# Z80TestCircuit.net
KiCad netlist of a schematic drawn in EAGLE
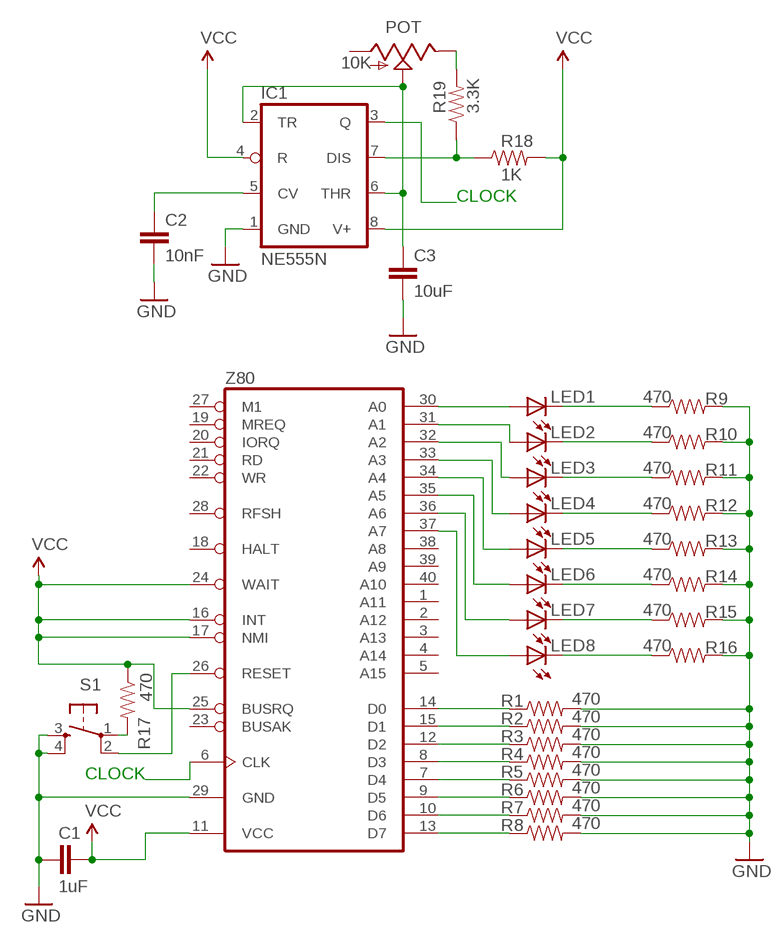
[diagram p0: schematic, sheet 1]

(export (version "E")
  (design (tool "Eeschema 10.0.6"))
  (components
    (comp (ref "C1")
      (value "1uF")
      (footprint "eagle-import:E5-5")
      (libsource (lib "eagle-import") (part "CAP"))
    )
    (comp (ref "C2")
      (value "10nF")
      (footprint "eagle-import:E5-5")
      (libsource (lib "eagle-import") (part "CAP"))
    )
    (comp (ref "C3")
      (value "10uF")
      (footprint "eagle-import:E5-5")
      (libsource (lib "eagle-import") (part "CAP"))
    )
    (comp (ref "IC1")
      (value "NE555N")
      (footprint "eagle-import:DIL08-ROUND")
      (libsource (lib "eagle-import") (part "555NNE"))
    )
    (comp (ref "LED1")
      (value "LED5MM")
      (footprint "eagle-import:LED5MM")
      (libsource (lib "eagle-import") (part "LED5MM"))
    )
    (comp (ref "LED2")
      (value "LED5MM")
      (footprint "eagle-import:LED5MM")
      (libsource (lib "eagle-import") (part "LED5MM"))
    )
    (comp (ref "LED3")
      (value "LED5MM")
      (footprint "eagle-import:LED5MM")
      (libsource (lib "eagle-import") (part "LED5MM"))
    )
    (comp (ref "LED4")
      (value "LED5MM")
      (footprint "eagle-import:LED5MM")
      (libsource (lib "eagle-import") (part "LED5MM"))
    )
    (comp (ref "LED5")
      (value "LED5MM")
      (footprint "eagle-import:LED5MM")
      (libsource (lib "eagle-import") (part "LED5MM"))
    )
    (comp (ref "LED6")
      (value "LED5MM")
      (footprint "eagle-import:LED5MM")
      (libsource (lib "eagle-import") (part "LED5MM"))
    )
    (comp (ref "LED7")
      (value "LED5MM")
      (footprint "eagle-import:LED5MM")
      (libsource (lib "eagle-import") (part "LED5MM"))
    )
    (comp (ref "LED8")
      (value "LED5MM")
      (footprint "eagle-import:LED5MM")
      (libsource (lib "eagle-import") (part "LED5MM"))
    )
    (comp (ref "POT")
      (value "10K")
      (footprint "eagle-import:POT_ALPHA_RV16AF-20")
      (libsource (lib "eagle-import") (part "POT-RV16AF-20"))
    )
    (comp (ref "R1")
      (value "470")
      (footprint "eagle-import:AXIAL-0.4")
      (libsource (lib "eagle-import") (part "RESISTORPTH-1/4W"))
    )
    (comp (ref "R2")
      (value "470")
      (footprint "eagle-import:AXIAL-0.4")
      (libsource (lib "eagle-import") (part "RESISTORPTH-1/4W"))
    )
    (comp (ref "R3")
      (value "470")
      (footprint "eagle-import:AXIAL-0.4")
      (libsource (lib "eagle-import") (part "RESISTORPTH-1/4W"))
    )
    (comp (ref "R4")
      (value "470")
      (footprint "eagle-import:AXIAL-0.4")
      (libsource (lib "eagle-import") (part "RESISTORPTH-1/4W"))
    )
    (comp (ref "R5")
      (value "470")
      (footprint "eagle-import:AXIAL-0.4")
      (libsource (lib "eagle-import") (part "RESISTORPTH-1/4W"))
    )
    (comp (ref "R6")
      (value "470")
      (footprint "eagle-import:AXIAL-0.4")
      (libsource (lib "eagle-import") (part "RESISTORPTH-1/4W"))
    )
    (comp (ref "R7")
      (value "470")
      (footprint "eagle-import:AXIAL-0.4")
      (libsource (lib "eagle-import") (part "RESISTORPTH-1/4W"))
    )
    (comp (ref "R8")
      (value "470")
      (footprint "eagle-import:AXIAL-0.4")
      (libsource (lib "eagle-import") (part "RESISTORPTH-1/4W"))
    )
    (comp (ref "R9")
      (value "470")
      (footprint "eagle-import:AXIAL-0.4")
      (libsource (lib "eagle-import") (part "RESISTORPTH-1/4W"))
    )
    (comp (ref "R10")
      (value "470")
      (footprint "eagle-import:AXIAL-0.4")
      (libsource (lib "eagle-import") (part "RESISTORPTH-1/4W"))
    )
    (comp (ref "R11")
      (value "470")
      (footprint "eagle-import:AXIAL-0.4")
      (libsource (lib "eagle-import") (part "RESISTORPTH-1/4W"))
    )
    (comp (ref "R12")
      (value "470")
      (footprint "eagle-import:AXIAL-0.4")
      (libsource (lib "eagle-import") (part "RESISTORPTH-1/4W"))
    )
    (comp (ref "R13")
      (value "470")
      (footprint "eagle-import:AXIAL-0.4")
      (libsource (lib "eagle-import") (part "RESISTORPTH-1/4W"))
    )
    (comp (ref "R14")
      (value "470")
      (footprint "eagle-import:AXIAL-0.4")
      (libsource (lib "eagle-import") (part "RESISTORPTH-1/4W"))
    )
    (comp (ref "R15")
      (value "470")
      (footprint "eagle-import:AXIAL-0.4")
      (libsource (lib "eagle-import") (part "RESISTORPTH-1/4W"))
    )
    (comp (ref "R16")
      (value "470")
      (footprint "eagle-import:AXIAL-0.4")
      (libsource (lib "eagle-import") (part "RESISTORPTH-1/4W"))
    )
    (comp (ref "R17")
      (value "470")
      (footprint "eagle-import:AXIAL-0.4")
      (libsource (lib "eagle-import") (part "RESISTORPTH-1/4W"))
    )
    (comp (ref "R18")
      (value "1K")
      (footprint "eagle-import:AXIAL-0.4")
      (libsource (lib "eagle-import") (part "RESISTORPTH-1/4W"))
    )
    (comp (ref "R19")
      (value "3.3K")
      (footprint "eagle-import:AXIAL-0.4")
      (libsource (lib "eagle-import") (part "RESISTORPTH-1/4W"))
    )
    (comp (ref "S1")
      (value "TAC_SWITCHPTH")
      (footprint "eagle-import:TACTILE-PTH")
      (libsource (lib "eagle-import") (part "TAC_SWITCHPTH"))
    )
    (comp (ref "Z80")
      (value "Z80CPU")
      (footprint "eagle-import:DIL40")
      (libsource (lib "eagle-import") (part "Z80CPU"))
    )
  )
  (nets
    (net (code "1") (name "GND") (class "Default")
      (node (ref "C1") (pin "-") (pinfunction "2_-") (pintype "passive"))
      (node (ref "C2") (pin "-") (pinfunction "2_-") (pintype "passive"))
      (node (ref "C3") (pin "-") (pinfunction "2_-") (pintype "passive"))
      (node (ref "IC1") (pin "1") (pinfunction "GND_1") (pintype "power_in"))
      (node (ref "R1") (pin "P$2") (pinfunction "2_P$2") (pintype "passive"))
      (node (ref "R10") (pin "P$2") (pinfunction "2_P$2") (pintype "passive"))
      (node (ref "R11") (pin "P$2") (pinfunction "2_P$2") (pintype "passive"))
      (node (ref "R12") (pin "P$2") (pinfunction "2_P$2") (pintype "passive"))
      (node (ref "R13") (pin "P$2") (pinfunction "2_P$2") (pintype "passive"))
      (node (ref "R14") (pin "P$2") (pinfunction "2_P$2") (pintype "passive"))
      (node (ref "R15") (pin "P$2") (pinfunction "2_P$2") (pintype "passive"))
      (node (ref "R16") (pin "P$2") (pinfunction "2_P$2") (pintype "passive"))
      (node (ref "R2") (pin "P$2") (pinfunction "2_P$2") (pintype "passive"))
      (node (ref "R3") (pin "P$2") (pinfunction "2_P$2") (pintype "passive"))
      (node (ref "R4") (pin "P$2") (pinfunction "2_P$2") (pintype "passive"))
      (node (ref "R5") (pin "P$2") (pinfunction "2_P$2") (pintype "passive"))
      (node (ref "R6") (pin "P$2") (pinfunction "2_P$2") (pintype "passive"))
      (node (ref "R7") (pin "P$2") (pinfunction "2_P$2") (pintype "passive"))
      (node (ref "R8") (pin "P$2") (pinfunction "2_P$2") (pintype "passive"))
      (node (ref "R9") (pin "P$2") (pinfunction "2_P$2") (pintype "passive"))
      (node (ref "S1") (pin "3") (pinfunction "3_3") (pintype "passive"))
      (node (ref "S1") (pin "4") (pinfunction "4_4") (pintype "passive"))
      (node (ref "Z80") (pin "29") (pinfunction "GND_29") (pintype "power_in"))
    )
    (net (code "2") (name "Net-(C2-1)") (class "Default")
      (node (ref "C2") (pin "+") (pinfunction "1_+") (pintype "passive"))
      (node (ref "IC1") (pin "5") (pinfunction "CV_5") (pintype "input"))
    )
    (net (code "3") (name "Net-(C3-1)") (class "Default")
      (node (ref "C3") (pin "+") (pinfunction "1_+") (pintype "passive"))
      (node (ref "IC1") (pin "2") (pinfunction "TR_2") (pintype "input"))
      (node (ref "IC1") (pin "6") (pinfunction "THR_6") (pintype "input"))
      (node (ref "POT") (pin "2") (pinfunction "S_2") (pintype "passive"))
    )
    (net (code "4") (name "Net-(IC1-DIS)") (class "Default")
      (node (ref "IC1") (pin "7") (pinfunction "DIS_7") (pintype "input"))
      (node (ref "R18") (pin "P$1") (pinfunction "1_P$1") (pintype "passive"))
      (node (ref "R19") (pin "P$1") (pinfunction "1_P$1") (pintype "passive"))
    )
    (net (code "5") (name "Net-(LED1-C)") (class "Default")
      (node (ref "LED1") (pin "K") (pinfunction "C_K") (pintype "passive"))
      (node (ref "R9") (pin "P$1") (pinfunction "1_P$1") (pintype "passive"))
    )
    (net (code "6") (name "Net-(LED2-C)") (class "Default")
      (node (ref "LED2") (pin "K") (pinfunction "C_K") (pintype "passive"))
      (node (ref "R10") (pin "P$1") (pinfunction "1_P$1") (pintype "passive"))
    )
    (net (code "7") (name "Net-(LED3-C)") (class "Default")
      (node (ref "LED3") (pin "K") (pinfunction "C_K") (pintype "passive"))
      (node (ref "R11") (pin "P$1") (pinfunction "1_P$1") (pintype "passive"))
    )
    (net (code "8") (name "Net-(LED4-C)") (class "Default")
      (node (ref "LED4") (pin "K") (pinfunction "C_K") (pintype "passive"))
      (node (ref "R12") (pin "P$1") (pinfunction "1_P$1") (pintype "passive"))
    )
    (net (code "9") (name "Net-(LED5-C)") (class "Default")
      (node (ref "LED5") (pin "K") (pinfunction "C_K") (pintype "passive"))
      (node (ref "R13") (pin "P$1") (pinfunction "1_P$1") (pintype "passive"))
    )
    (net (code "10") (name "Net-(LED6-C)") (class "Default")
      (node (ref "LED6") (pin "K") (pinfunction "C_K") (pintype "passive"))
      (node (ref "R14") (pin "P$1") (pinfunction "1_P$1") (pintype "passive"))
    )
    (net (code "11") (name "Net-(LED7-C)") (class "Default")
      (node (ref "LED7") (pin "K") (pinfunction "C_K") (pintype "passive"))
      (node (ref "R15") (pin "P$1") (pinfunction "1_P$1") (pintype "passive"))
    )
    (net (code "12") (name "Net-(LED8-C)") (class "Default")
      (node (ref "LED8") (pin "K") (pinfunction "C_K") (pintype "passive"))
      (node (ref "R16") (pin "P$1") (pinfunction "1_P$1") (pintype "passive"))
    )
    (net (code "13") (name "Net-(POT-E)") (class "Default")
      (node (ref "POT") (pin "3") (pinfunction "E_3") (pintype "passive"))
      (node (ref "R19") (pin "P$2") (pinfunction "2_P$2") (pintype "passive"))
    )
    (net (code "14") (name "Net-(R1-1)") (class "Default")
      (node (ref "R1") (pin "P$1") (pinfunction "1_P$1") (pintype "passive"))
      (node (ref "Z80") (pin "14") (pinfunction "D0_14") (pintype "bidirectional"))
    )
    (net (code "15") (name "Net-(R2-1)") (class "Default")
      (node (ref "R2") (pin "P$1") (pinfunction "1_P$1") (pintype "passive"))
      (node (ref "Z80") (pin "15") (pinfunction "D1_15") (pintype "bidirectional"))
    )
    (net (code "16") (name "Net-(R3-1)") (class "Default")
      (node (ref "R3") (pin "P$1") (pinfunction "1_P$1") (pintype "passive"))
      (node (ref "Z80") (pin "12") (pinfunction "D2_12") (pintype "bidirectional"))
    )
    (net (code "17") (name "Net-(R4-1)") (class "Default")
      (node (ref "R4") (pin "P$1") (pinfunction "1_P$1") (pintype "passive"))
      (node (ref "Z80") (pin "8") (pinfunction "D3_8") (pintype "bidirectional"))
    )
    (net (code "18") (name "Net-(R5-1)") (class "Default")
      (node (ref "R5") (pin "P$1") (pinfunction "1_P$1") (pintype "passive"))
      (node (ref "Z80") (pin "7") (pinfunction "D4_7") (pintype "bidirectional"))
    )
    (net (code "19") (name "Net-(R6-1)") (class "Default")
      (node (ref "R6") (pin "P$1") (pinfunction "1_P$1") (pintype "passive"))
      (node (ref "Z80") (pin "9") (pinfunction "D5_9") (pintype "bidirectional"))
    )
    (net (code "20") (name "Net-(R7-1)") (class "Default")
      (node (ref "R7") (pin "P$1") (pinfunction "1_P$1") (pintype "passive"))
      (node (ref "Z80") (pin "10") (pinfunction "D6_10") (pintype "bidirectional"))
    )
    (net (code "21") (name "Net-(R8-1)") (class "Default")
      (node (ref "R8") (pin "P$1") (pinfunction "1_P$1") (pintype "passive"))
      (node (ref "Z80") (pin "13") (pinfunction "D7_13") (pintype "bidirectional"))
    )
    (net (code "22") (name "Net-(R17-2)") (class "Default")
      (node (ref "R17") (pin "P$2") (pinfunction "2_P$2") (pintype "passive"))
      (node (ref "S1") (pin "1") (pinfunction "1_1") (pintype "passive"))
    )
    (net (code "23") (name "Net-(Z80-A0)") (class "Default")
      (node (ref "LED1") (pin "A") (pinfunction "A_A") (pintype "passive"))
      (node (ref "Z80") (pin "30") (pinfunction "A0_30") (pintype "output"))
    )
    (net (code "24") (name "Net-(Z80-A1)") (class "Default")
      (node (ref "LED2") (pin "A") (pinfunction "A_A") (pintype "passive"))
      (node (ref "Z80") (pin "31") (pinfunction "A1_31") (pintype "output"))
    )
    (net (code "25") (name "Net-(Z80-A2)") (class "Default")
      (node (ref "LED3") (pin "A") (pinfunction "A_A") (pintype "passive"))
      (node (ref "Z80") (pin "32") (pinfunction "A2_32") (pintype "output"))
    )
    (net (code "26") (name "Net-(Z80-A3)") (class "Default")
      (node (ref "LED4") (pin "A") (pinfunction "A_A") (pintype "passive"))
      (node (ref "Z80") (pin "33") (pinfunction "A3_33") (pintype "output"))
    )
    (net (code "27") (name "Net-(Z80-A4)") (class "Default")
      (node (ref "LED5") (pin "A") (pinfunction "A_A") (pintype "passive"))
      (node (ref "Z80") (pin "34") (pinfunction "A4_34") (pintype "output"))
    )
    (net (code "28") (name "Net-(Z80-A5)") (class "Default")
      (node (ref "LED6") (pin "A") (pinfunction "A_A") (pintype "passive"))
      (node (ref "Z80") (pin "35") (pinfunction "A5_35") (pintype "output"))
    )
    (net (code "29") (name "Net-(Z80-A6)") (class "Default")
      (node (ref "LED7") (pin "A") (pinfunction "A_A") (pintype "passive"))
      (node (ref "Z80") (pin "36") (pinfunction "A6_36") (pintype "output"))
    )
    (net (code "30") (name "Net-(Z80-A7)") (class "Default")
      (node (ref "LED8") (pin "A") (pinfunction "A_A") (pintype "passive"))
      (node (ref "Z80") (pin "37") (pinfunction "A7_37") (pintype "output"))
    )
    (net (code "31") (name "Net-(Z80-RESET)") (class "Default")
      (node (ref "S1") (pin "2") (pinfunction "2_2") (pintype "passive"))
      (node (ref "Z80") (pin "26") (pinfunction "RESET_26") (pintype "input"))
    )
    (net (code "32") (name "VCC") (class "Default")
      (node (ref "C1") (pin "+") (pinfunction "1_+") (pintype "passive"))
      (node (ref "IC1") (pin "4") (pinfunction "R_4") (pintype "input"))
      (node (ref "IC1") (pin "8") (pinfunction "V+_8") (pintype "power_in"))
      (node (ref "R17") (pin "P$1") (pinfunction "1_P$1") (pintype "passive"))
      (node (ref "R18") (pin "P$2") (pinfunction "2_P$2") (pintype "passive"))
      (node (ref "Z80") (pin "11") (pinfunction "VCC_11") (pintype "power_in"))
      (node (ref "Z80") (pin "16") (pinfunction "INT_16") (pintype "input"))
      (node (ref "Z80") (pin "17") (pinfunction "NMI_17") (pintype "input"))
      (node (ref "Z80") (pin "24") (pinfunction "WAIT_24") (pintype "input"))
      (node (ref "Z80") (pin "25") (pinfunction "BUSRQ_25") (pintype "input"))
    )
    (net (code "33") (name "unconnected-(IC1-Q-Pad3)") (class "Default")
      (node (ref "IC1") (pin "3") (pinfunction "Q_3") (pintype "output"))
    )
    (net (code "34") (name "unconnected-(POT-A-Pad1)") (class "Default")
      (node (ref "POT") (pin "1") (pinfunction "A_1") (pintype "passive"))
    )
    (net (code "35") (name "unconnected-(Z80-A8-Pad38)") (class "Default")
      (node (ref "Z80") (pin "38") (pinfunction "A8_38") (pintype "output"))
    )
    (net (code "36") (name "unconnected-(Z80-A9-Pad39)") (class "Default")
      (node (ref "Z80") (pin "39") (pinfunction "A9_39") (pintype "output"))
    )
    (net (code "37") (name "unconnected-(Z80-A10-Pad40)") (class "Default")
      (node (ref "Z80") (pin "40") (pinfunction "A10_40") (pintype "output"))
    )
    (net (code "38") (name "unconnected-(Z80-A11-Pad1)") (class "Default")
      (node (ref "Z80") (pin "1") (pinfunction "A11_1") (pintype "output"))
    )
    (net (code "39") (name "unconnected-(Z80-A12-Pad2)") (class "Default")
      (node (ref "Z80") (pin "2") (pinfunction "A12_2") (pintype "output"))
    )
    (net (code "40") (name "unconnected-(Z80-A13-Pad3)") (class "Default")
      (node (ref "Z80") (pin "3") (pinfunction "A13_3") (pintype "output"))
    )
    (net (code "41") (name "unconnected-(Z80-A14-Pad4)") (class "Default")
      (node (ref "Z80") (pin "4") (pinfunction "A14_4") (pintype "output"))
    )
    (net (code "42") (name "unconnected-(Z80-A15-Pad5)") (class "Default")
      (node (ref "Z80") (pin "5") (pinfunction "A15_5") (pintype "output"))
    )
    (net (code "43") (name "unconnected-(Z80-BUSAK-Pad23)") (class "Default")
      (node (ref "Z80") (pin "23") (pinfunction "BUSAK_23") (pintype "output"))
    )
    (net (code "44") (name "unconnected-(Z80-CLK-Pad6)") (class "Default")
      (node (ref "Z80") (pin "6") (pinfunction "CLK_6") (pintype "input"))
    )
    (net (code "45") (name "unconnected-(Z80-HALT-Pad18)") (class "Default")
      (node (ref "Z80") (pin "18") (pinfunction "HALT_18") (pintype "output"))
    )
    (net (code "46") (name "unconnected-(Z80-IORQ-Pad20)") (class "Default")
      (node (ref "Z80") (pin "20") (pinfunction "IORQ_20") (pintype "output"))
    )
    (net (code "47") (name "unconnected-(Z80-M1-Pad27)") (class "Default")
      (node (ref "Z80") (pin "27") (pinfunction "M1_27") (pintype "output"))
    )
    (net (code "48") (name "unconnected-(Z80-MREQ-Pad19)") (class "Default")
      (node (ref "Z80") (pin "19") (pinfunction "MREQ_19") (pintype "output"))
    )
    (net (code "49") (name "unconnected-(Z80-RD-Pad21)") (class "Default")
      (node (ref "Z80") (pin "21") (pinfunction "RD_21") (pintype "output"))
    )
    (net (code "50") (name "unconnected-(Z80-RFSH-Pad28)") (class "Default")
      (node (ref "Z80") (pin "28") (pinfunction "RFSH_28") (pintype "output"))
    )
    (net (code "51") (name "unconnected-(Z80-WR-Pad22)") (class "Default")
      (node (ref "Z80") (pin "22") (pinfunction "WR_22") (pintype "output"))
    )
  )
)
